# ATK_BC28_02.net
KiCad netlist of a schematic drawn in Altium Designer
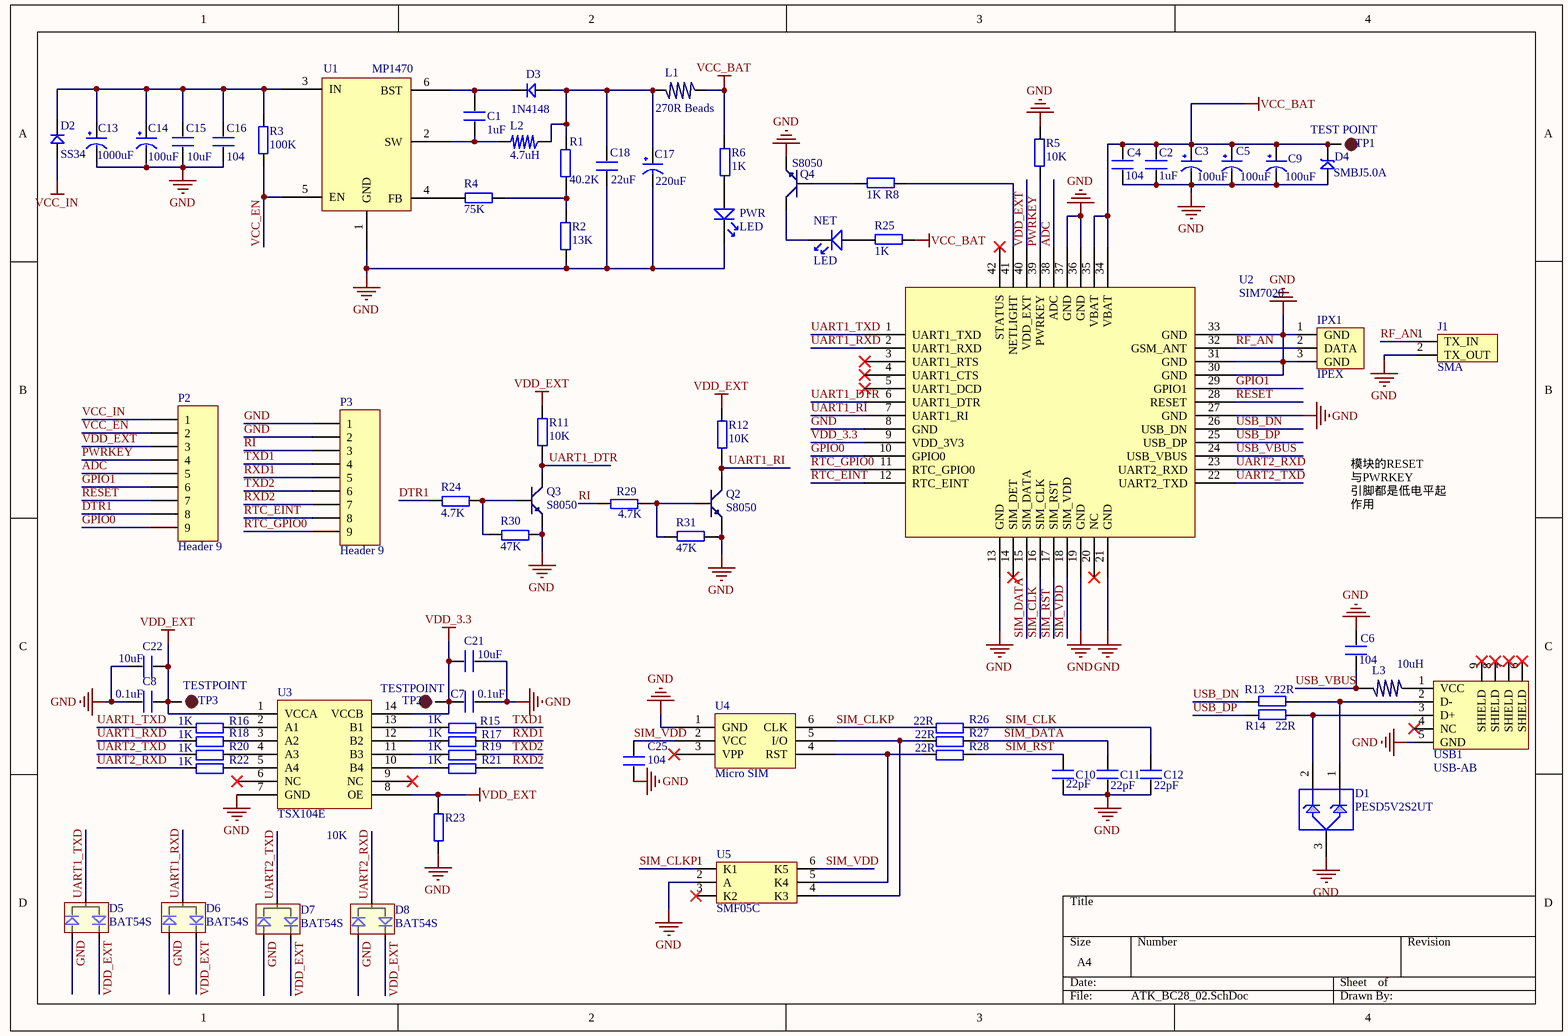
[diagram p0: ATK_BC28_02.SchDoc]

(export (version "E")
  (design (tool "Eeschema 10.0.6"))
  (components
    (comp (ref "C1") (value "1uF") (footprint "0603P") (libsource (lib "SIM7020") (part "C")))
    (comp (ref "C2") (value "1uF") (footprint "0603P") (libsource (lib "SIM7020") (part "C")))
    (comp (ref "C3") (value "100uF") (footprint "C3528") (libsource (lib "SIM7020") (part "CAP")))
    (comp (ref "C4") (value "104") (footprint "0603P") (libsource (lib "ALIENTEK_COMPONENT") (part "C")))
    (comp (ref "C5") (value "100uF") (footprint "C3528") (libsource (lib "SIM7020") (part "CAP")))
    (comp (ref "C6") (value "104") (footprint "0603P") (libsource (lib "ALIENTEK_COMPONENT") (part "C")))
    (comp (ref "C7") (value "0.1uF") (footprint "0603P") (libsource (lib "SIM7020") (part "C")))
    (comp (ref "C8") (value "0.1uF") (footprint "0603P") (libsource (lib "SIM7020") (part "C")))
    (comp (ref "C9") (value "100uF") (footprint "C3528") (libsource (lib "SIM7020") (part "CAP")))
    (comp (ref "C10") (value "22pF") (footprint "0402") (libsource (lib "ALIENTEK_COMPONENT") (part "C")))
    (comp (ref "C11") (value "22pF") (footprint "0402") (libsource (lib "ALIENTEK_COMPONENT") (part "C")))
    (comp (ref "C12") (value "22pF") (footprint "0402") (libsource (lib "ALIENTEK_COMPONENT") (part "C")))
    (comp (ref "C13")
      (value "1000uF")
      (footprint "CAP2.54")
      (libsource (lib "ALIENTEK_COMPONENT") (part "CAP"))
    )
    (comp (ref "C14") (value "100uF") (footprint "C3528") (libsource (lib "ALIENTEK_COMPONENT") (part "CAP")))
    (comp (ref "C15") (value "10uF") (footprint "0805") (libsource (lib "SIM7020") (part "C")))
    (comp (ref "C16") (value "104") (footprint "0603P") (libsource (lib "SIM7020") (part "C")))
    (comp (ref "C17") (value "220uF") (footprint "CC6.56.5") (libsource (lib "SIM7020") (part "CAP")))
    (comp (ref "C18") (value "22uF") (footprint "1206") (libsource (lib "SIM7020") (part "C")))
    (comp (ref "C21") (value "10uF") (footprint "0603P") (libsource (lib "SIM7020") (part "C")))
    (comp (ref "C22") (value "10uF") (footprint "0603P") (libsource (lib "SIM7020") (part "C")))
    (comp (ref "C25") (value "104") (footprint "0603P") (libsource (lib "ALIENTEK_COMPONENT") (part "C")))
    (comp (ref "D1")
      (value "PESD5V2S2UT")
      (footprint "SOT-23")
      (description "PESD5V2S2UT,SOT-23,NXP")
      (fields (field (name "Comment") "ESD-3"))
      (libsource (lib "02.MCU_KL25") (part "ESD-3"))
    )
    (comp (ref "D2")
      (value "SS34")
      (footprint "DIODE_3*5.3")
      (description "1N4148")
      (libsource (lib "alientek_sch_lib") (part "D"))
    )
    (comp (ref "D3") (value "1N4148") (footprint "DIODE_SOP") (libsource (lib "alientek_sch_lib") (part "D")))
    (comp (ref "D4")
      (value "SMBJ5.0A")
      (footprint "SMBJ")
      (description "TVS")
      (libsource (lib "ALIENTEK_COMPONENT") (part "SMBJ"))
    )
    (comp (ref "D5")
      (value "BAT54S")
      (footprint "SOT-23")
      (description "双肖特基二极管")
      (libsource (lib "ALIENTEK_COMPONENT") (part "BAT54S"))
    )
    (comp (ref "D6")
      (value "BAT54S")
      (footprint "SOT-23")
      (description "双肖特基二极管")
      (libsource (lib "ALIENTEK_COMPONENT") (part "BAT54S"))
    )
    (comp (ref "D7")
      (value "BAT54S")
      (footprint "SOT-23")
      (description "双肖特基二极管")
      (libsource (lib "ALIENTEK_COMPONENT") (part "BAT54S"))
    )
    (comp (ref "D8")
      (value "BAT54S")
      (footprint "SOT-23")
      (description "双肖特基二极管")
      (libsource (lib "ALIENTEK_COMPONENT") (part "BAT54S"))
    )
    (comp (ref "IPX1")
      (value "IPEX")
      (footprint "IPEX")
      (description "IPEX座")
      (libsource (lib "ATK_S1216F8_BD_V1.1") (part "IPEX"))
    )
    (comp (ref "J1")
      (value "SMA")
      (footprint "SMA-2")
      (description "SMA-2")
      (libsource (lib "SIM7020") (part "SMA-2"))
    )
    (comp (ref "L1") (value "270R Beads") (footprint "1206") (libsource (lib "SIM7020") (part "L")))
    (comp (ref "L2")
      (value "4.7uH")
      (footprint "L_CD43")
      (libsource (lib "ATK-7'TFTLCD电容触摸屏模块_V2.2") (part "L_SOP"))
    )
    (comp (ref "L3") (value "10uH") (footprint "0805") (libsource (lib "ALIENTEK_COMPONENT") (part "L")))
    (comp (ref "NET") (value "LED") (footprint "SMDLED") (libsource (lib "SIM7020") (part "LED")))
    (comp (ref "P2")
      (value "Header 9")
      (footprint "HDR1X9")
      (description "Header, 9-Pin")
      (fields (field (name "PUBLISHER") "Altium Limited"))
      (libsource (lib "Miscellaneous Connectors") (part "Header 9"))
    )
    (comp (ref "P3")
      (value "Header 9")
      (footprint "HDR1X9")
      (description "Header, 9-Pin")
      (fields (field (name "PUBLISHER") "Altium Limited"))
      (libsource (lib "Miscellaneous Connectors") (part "Header 9"))
    )
    (comp (ref "PWR") (value "LED") (footprint "SMDLED") (libsource (lib "SIM7020") (part "LED")))
    (comp (ref "Q2")
      (value "S8050")
      (footprint "SOT-23R")
      (description "8050/BCW846/BCW847")
      (libsource (lib "SIM7020") (part "NPN"))
    )
    (comp (ref "Q3")
      (value "S8050")
      (footprint "SOT-23R")
      (description "8050/BCW846/BCW847")
      (libsource (lib "SIM7020") (part "NPN"))
    )
    (comp (ref "Q4")
      (value "S8050")
      (footprint "SOT-23R")
      (description "8050/BCW846/BCW847")
      (libsource (lib "SIM7020") (part "NPN"))
    )
    (comp (ref "R1") (value "40.2K") (footprint "0603P") (libsource (lib "ALIENTEK_COMPONENT") (part "R")))
    (comp (ref "R2") (value "13K") (footprint "0603P") (libsource (lib "ALIENTEK_COMPONENT") (part "R")))
    (comp (ref "R3") (value "100K") (footprint "0603P") (libsource (lib "ALIENTEK_COMPONENT") (part "R")))
    (comp (ref "R4") (value "75K") (footprint "0603P") (libsource (lib "ALIENTEK_COMPONENT") (part "R")))
    (comp (ref "R5") (value "10K") (footprint "0603P") (libsource (lib "ALIENTEK_COMPONENT") (part "R")))
    (comp (ref "R6") (value "1K") (footprint "0603P") (libsource (lib "ALIENTEK_COMPONENT") (part "R")))
    (comp (ref "R8") (value "1K") (footprint "0603P") (libsource (lib "ALIENTEK_COMPONENT") (part "R")))
    (comp (ref "R11") (value "10K") (footprint "0603P") (libsource (lib "ALIENTEK_COMPONENT") (part "R")))
    (comp (ref "R12") (value "10K") (footprint "0603P") (libsource (lib "ALIENTEK_COMPONENT") (part "R")))
    (comp (ref "R13") (value "22R") (footprint "0603P") (libsource (lib "SIM7020") (part "R")))
    (comp (ref "R14") (value "22R") (footprint "0603P") (libsource (lib "SIM7020") (part "R")))
    (comp (ref "R15") (value "1K") (footprint "0603P") (libsource (lib "SIM7020") (part "R")))
    (comp (ref "R16") (value "1K") (footprint "0603P") (libsource (lib "SIM7020") (part "R")))
    (comp (ref "R17") (value "1K") (footprint "0603P") (libsource (lib "SIM7020") (part "R")))
    (comp (ref "R18") (value "1K") (footprint "0603P") (libsource (lib "SIM7020") (part "R")))
    (comp (ref "R19") (value "1K") (footprint "0603P") (libsource (lib "SIM7020") (part "R")))
    (comp (ref "R20") (value "1K") (footprint "0603P") (libsource (lib "SIM7020") (part "R")))
    (comp (ref "R21") (value "1K") (footprint "0603P") (libsource (lib "SIM7020") (part "R")))
    (comp (ref "R22") (value "1K") (footprint "0603P") (libsource (lib "SIM7020") (part "R")))
    (comp (ref "R23") (value "10K") (footprint "0603P") (libsource (lib "SIM7020") (part "R")))
    (comp (ref "R24") (value "4.7K") (footprint "0603P") (libsource (lib "ALIENTEK_COMPONENT") (part "R")))
    (comp (ref "R25") (value "1K") (footprint "0603P") (libsource (lib "ALIENTEK_COMPONENT") (part "R")))
    (comp (ref "R26") (value "22R") (footprint "0603P") (libsource (lib "SIM7020") (part "R")))
    (comp (ref "R27") (value "22R") (footprint "0603P") (libsource (lib "SIM7020") (part "R")))
    (comp (ref "R28") (value "22R") (footprint "0603P") (libsource (lib "SIM7020") (part "R")))
    (comp (ref "R29") (value "4.7K") (footprint "0603P") (libsource (lib "ALIENTEK_COMPONENT") (part "R")))
    (comp (ref "R30") (value "47K") (footprint "0603P") (libsource (lib "ALIENTEK_COMPONENT") (part "R")))
    (comp (ref "R31") (value "47K") (footprint "0603P") (libsource (lib "ALIENTEK_COMPONENT") (part "R")))
    (comp (ref "TP1")
      (value "TEST POINT")
      (footprint "TP-1.5")
      (description "测试点")
      (libsource (lib "ALIENTEK_COMPONENT") (part "TEST-POINT"))
    )
    (comp (ref "TP2")
      (value "TESTPOINT")
      (footprint "TP-1.5")
      (description "测试点")
      (libsource (lib "ALIENTEK_COMPONENT") (part "TEST-POINT"))
    )
    (comp (ref "TP3")
      (value "TESTPOINT")
      (footprint "TP-1.5")
      (description "测试点")
      (libsource (lib "ALIENTEK_COMPONENT") (part "TEST-POINT"))
    )
    (comp (ref "U1")
      (value "MP1470")
      (footprint "SOP23-6 - duplicate1")
      (libsource (lib "SIM7020") (part "MP1470"))
    )
    (comp (ref "U2")
      (value "SIM7020")
      (footprint "SIM7020")
      (description "NBloT")
      (libsource (lib "SIM7020") (part "SIM7020"))
    )
    (comp (ref "U3") (value "TSX104E") (footprint "TSX104E") (libsource (lib "SIM7020") (part "TSX104E")))
    (comp (ref "U4") (value "Micro SIM") (footprint "Micro SIM") (libsource (lib "plib") (part "Micro SIM")))
    (comp (ref "U5")
      (value "SMF05C")
      (footprint "SMF05C")
      (description "TVS")
      (libsource (lib "plib") (part "SMF05C"))
    )
    (comp (ref "USB1")
      (value "USB-AB")
      (footprint "USB_AB")
      (description "MicroUSB")
      (libsource (lib "ALIENTEK_COMPONENT") (part "USB-AB"))
    )
  )
  (nets
    (net (code "1") (name "/ADC") (class "Default")
      (node (ref "P2") (pin "5") (pinfunction "5_5") (pintype "passive"))
      (node (ref "U2") (pin "38") (pinfunction "ADC_38") (pintype "passive"))
    )
    (net (code "2") (name "/DTR1") (class "Default")
      (node (ref "P2") (pin "8") (pinfunction "8_8") (pintype "passive"))
      (node (ref "R24") (pin "1") (pintype "passive"))
    )
    (net (code "3") (name "/GPIO0") (class "Default")
      (node (ref "P2") (pin "9") (pinfunction "9_9") (pintype "passive"))
      (node (ref "U2") (pin "10") (pinfunction "GPIO0_10") (pintype "passive"))
    )
    (net (code "4") (name "/GPIO1") (class "Default")
      (node (ref "P2") (pin "6") (pinfunction "6_6") (pintype "passive"))
      (node (ref "U2") (pin "29") (pinfunction "GPIO1_29") (pintype "passive"))
    )
    (net (code "5") (name "/PWRKEY") (class "Default")
      (node (ref "P2") (pin "4") (pinfunction "4_4") (pintype "passive"))
      (node (ref "R5") (pin "2") (pintype "passive"))
      (node (ref "U2") (pin "39") (pinfunction "PWRKEY_39") (pintype "passive"))
    )
    (net (code "6") (name "/RESET") (class "Default")
      (node (ref "P2") (pin "7") (pinfunction "7_7") (pintype "passive"))
      (node (ref "U2") (pin "28") (pinfunction "RESET_28") (pintype "passive"))
    )
    (net (code "7") (name "/RF_AN") (class "Default")
      (node (ref "IPX1") (pin "2") (pinfunction "DATA_2") (pintype "passive"))
      (node (ref "J1") (pin "1") (pinfunction "TX_IN_1") (pintype "passive"))
      (node (ref "U2") (pin "32") (pinfunction "GSM_ANT_32") (pintype "passive"))
    )
    (net (code "8") (name "/RI") (class "Default")
      (node (ref "P3") (pin "3") (pinfunction "3_3") (pintype "passive"))
      (node (ref "R29") (pin "1") (pintype "passive"))
    )
    (net (code "9") (name "/RTC_EINT") (class "Default")
      (node (ref "P3") (pin "8") (pinfunction "8_8") (pintype "passive"))
      (node (ref "U2") (pin "12") (pinfunction "RTC_EINT_12") (pintype "passive"))
    )
    (net (code "10") (name "/RTC_GPIO0") (class "Default")
      (node (ref "P3") (pin "9") (pinfunction "9_9") (pintype "passive"))
      (node (ref "U2") (pin "11") (pinfunction "RTC_GPIO0_11") (pintype "passive"))
    )
    (net (code "11") (name "/RXD1") (class "Default")
      (node (ref "P3") (pin "5") (pinfunction "5_5") (pintype "passive"))
      (node (ref "R17") (pin "2") (pintype "passive"))
    )
    (net (code "12") (name "/RXD2") (class "Default")
      (node (ref "P3") (pin "7") (pinfunction "7_7") (pintype "passive"))
      (node (ref "R21") (pin "2") (pintype "passive"))
    )
    (net (code "13") (name "/SIM_CLK") (class "Default")
      (node (ref "C12") (pin "2") (pintype "passive"))
      (node (ref "R26") (pin "2") (pintype "passive"))
      (node (ref "U2") (pin "16") (pinfunction "SIM_CLK_16") (pintype "passive"))
    )
    (net (code "14") (name "/SIM_CLKP") (class "Default")
      (node (ref "R26") (pin "1") (pintype "passive"))
      (node (ref "U4") (pin "6") (pinfunction "CLK_6") (pintype "passive"))
      (node (ref "U5") (pin "1") (pinfunction "K1_1") (pintype "passive"))
    )
    (net (code "15") (name "/SIM_DATA") (class "Default")
      (node (ref "C11") (pin "2") (pintype "passive"))
      (node (ref "R27") (pin "2") (pintype "passive"))
      (node (ref "U2") (pin "15") (pinfunction "SIM_DATA_15") (pintype "passive"))
    )
    (net (code "16") (name "/SIM_RST") (class "Default")
      (node (ref "C10") (pin "1") (pintype "passive"))
      (node (ref "R28") (pin "2") (pintype "passive"))
      (node (ref "U2") (pin "17") (pinfunction "SIM_RST_17") (pintype "passive"))
    )
    (net (code "17") (name "/SIM_VDD") (class "Default")
      (node (ref "C25") (pin "2") (pintype "passive"))
      (node (ref "U2") (pin "18") (pinfunction "SIM_VDD_18") (pintype "passive"))
      (node (ref "U4") (pin "2") (pinfunction "VCC_2") (pintype "passive"))
      (node (ref "U5") (pin "6") (pinfunction "K5_6") (pintype "passive"))
    )
    (net (code "18") (name "/TXD1") (class "Default")
      (node (ref "P3") (pin "4") (pinfunction "4_4") (pintype "passive"))
      (node (ref "R15") (pin "2") (pintype "passive"))
    )
    (net (code "19") (name "/TXD2") (class "Default")
      (node (ref "P3") (pin "6") (pinfunction "6_6") (pintype "passive"))
      (node (ref "R19") (pin "2") (pintype "passive"))
    )
    (net (code "20") (name "/UART1_DTR") (class "Default")
      (node (ref "Q3") (pin "3") (pinfunction "C_3") (pintype "passive"))
      (node (ref "R11") (pin "1") (pintype "passive"))
      (node (ref "U2") (pin "6") (pinfunction "UART1_DTR_6") (pintype "passive"))
    )
    (net (code "21") (name "/UART1_RI") (class "Default")
      (node (ref "Q2") (pin "3") (pinfunction "C_3") (pintype "passive"))
      (node (ref "R12") (pin "1") (pintype "passive"))
      (node (ref "U2") (pin "7") (pinfunction "UART1_RI_7") (pintype "passive"))
    )
    (net (code "22") (name "/UART1_RXD") (class "Default")
      (node (ref "D6") (pin "3") (pintype "passive"))
      (node (ref "R18") (pin "1") (pintype "passive"))
      (node (ref "U2") (pin "2") (pinfunction "UART1_RXD_2") (pintype "passive"))
    )
    (net (code "23") (name "/UART1_TXD") (class "Default")
      (node (ref "D5") (pin "3") (pintype "passive"))
      (node (ref "R16") (pin "1") (pintype "passive"))
      (node (ref "U2") (pin "1") (pinfunction "UART1_TXD_1") (pintype "passive"))
    )
    (net (code "24") (name "/UART2_RXD") (class "Default")
      (node (ref "D8") (pin "3") (pintype "passive"))
      (node (ref "R22") (pin "1") (pintype "passive"))
      (node (ref "U2") (pin "23") (pinfunction "UART2_RXD_23") (pintype "passive"))
    )
    (net (code "25") (name "/UART2_TXD") (class "Default")
      (node (ref "D7") (pin "3") (pintype "passive"))
      (node (ref "R20") (pin "1") (pintype "passive"))
      (node (ref "U2") (pin "22") (pinfunction "UART2_TXD_22") (pintype "passive"))
    )
    (net (code "26") (name "/USB_DN") (class "Default")
      (node (ref "R13") (pin "2") (pintype "passive"))
      (node (ref "U2") (pin "26") (pinfunction "USB_DN_26") (pintype "passive"))
    )
    (net (code "27") (name "/USB_DP") (class "Default")
      (node (ref "R14") (pin "2") (pintype "passive"))
      (node (ref "U2") (pin "25") (pinfunction "USB_DP_25") (pintype "passive"))
    )
    (net (code "28") (name "/USB_VBUS") (class "Default")
      (node (ref "C6") (pin "1") (pintype "passive"))
      (node (ref "L3") (pin "2") (pintype "passive"))
      (node (ref "U2") (pin "24") (pinfunction "USB_VBUS_24") (pintype "passive"))
    )
    (net (code "29") (name "/VCC_EN") (class "Default")
      (node (ref "P2") (pin "2") (pinfunction "2_2") (pintype "passive"))
      (node (ref "R3") (pin "2") (pintype "passive"))
      (node (ref "U1") (pin "5") (pinfunction "EN_5") (pintype "passive"))
    )
    (net (code "30") (name "GND") (class "Default")
      (node (ref "C10") (pin "2") (pintype "passive"))
      (node (ref "C11") (pin "1") (pintype "passive"))
      (node (ref "C12") (pin "1") (pintype "passive"))
      (node (ref "C13") (pin "2") (pinfunction "GND_2") (pintype "passive"))
      (node (ref "C14") (pin "2") (pinfunction "GND_2") (pintype "passive"))
      (node (ref "C15") (pin "2") (pintype "passive"))
      (node (ref "C16") (pin "1") (pintype "passive"))
      (node (ref "C17") (pin "2") (pinfunction "GND_2") (pintype "passive"))
      (node (ref "C18") (pin "1") (pintype "passive"))
      (node (ref "C2") (pin "1") (pintype "passive"))
      (node (ref "C21") (pin "2") (pintype "passive"))
      (node (ref "C22") (pin "1") (pintype "passive"))
      (node (ref "C25") (pin "1") (pintype "passive"))
      (node (ref "C3") (pin "2") (pinfunction "GND_2") (pintype "passive"))
      (node (ref "C4") (pin "1") (pintype "passive"))
      (node (ref "C5") (pin "2") (pinfunction "GND_2") (pintype "passive"))
      (node (ref "C6") (pin "2") (pintype "passive"))
      (node (ref "C7") (pin "2") (pintype "passive"))
      (node (ref "C8") (pin "2") (pintype "passive"))
      (node (ref "C9") (pin "2") (pinfunction "GND_2") (pintype "passive"))
      (node (ref "D1") (pin "3") (pinfunction "3_3") (pintype "passive"))
      (node (ref "D4") (pin "1") (pintype "passive"))
      (node (ref "D5") (pin "1") (pintype "passive"))
      (node (ref "D6") (pin "1") (pintype "passive"))
      (node (ref "D7") (pin "1") (pintype "passive"))
      (node (ref "D8") (pin "1") (pintype "passive"))
      (node (ref "IPX1") (pin "1") (pinfunction "GND_1") (pintype "passive"))
      (node (ref "IPX1") (pin "3") (pinfunction "GND_3") (pintype "passive"))
      (node (ref "J1") (pin "2") (pinfunction "TX_OUT_2") (pintype "passive"))
      (node (ref "P3") (pin "1") (pinfunction "1_1") (pintype "passive"))
      (node (ref "P3") (pin "2") (pinfunction "2_2") (pintype "passive"))
      (node (ref "PWR") (pin "2") (pinfunction "2_2") (pintype "passive"))
      (node (ref "Q2") (pin "1") (pinfunction "E_1") (pintype "passive"))
      (node (ref "Q3") (pin "1") (pinfunction "E_1") (pintype "passive"))
      (node (ref "Q4") (pin "1") (pinfunction "E_1") (pintype "passive"))
      (node (ref "R2") (pin "2") (pintype "passive"))
      (node (ref "R23") (pin "1") (pintype "passive"))
      (node (ref "R30") (pin "2") (pintype "passive"))
      (node (ref "R31") (pin "1") (pintype "passive"))
      (node (ref "R5") (pin "1") (pintype "passive"))
      (node (ref "U1") (pin "1") (pinfunction "GND_1") (pintype "passive"))
      (node (ref "U2") (pin "13") (pinfunction "GND_13") (pintype "passive"))
      (node (ref "U2") (pin "19") (pinfunction "GND_19") (pintype "passive"))
      (node (ref "U2") (pin "21") (pinfunction "GND_21") (pintype "passive"))
      (node (ref "U2") (pin "27") (pinfunction "GND_27") (pintype "passive"))
      (node (ref "U2") (pin "30") (pinfunction "GND_30") (pintype "passive"))
      (node (ref "U2") (pin "31") (pinfunction "GND_31") (pintype "passive"))
      (node (ref "U2") (pin "33") (pinfunction "GND_33") (pintype "passive"))
      (node (ref "U2") (pin "36") (pinfunction "GND_36") (pintype "passive"))
      (node (ref "U2") (pin "37") (pinfunction "GND_37") (pintype "passive"))
      (node (ref "U2") (pin "8") (pinfunction "GND_8") (pintype "passive"))
      (node (ref "U3") (pin "7") (pinfunction "GND_7") (pintype "passive"))
      (node (ref "U4") (pin "1") (pinfunction "GND_1") (pintype "passive"))
      (node (ref "U5") (pin "2") (pinfunction "A_2") (pintype "passive"))
      (node (ref "USB1") (pin "5") (pinfunction "GND_5") (pintype "passive"))
    )
    (net (code "31") (name "Net-(C13-VCC)") (class "Default")
      (node (ref "C13") (pin "1") (pinfunction "VCC_1") (pintype "passive"))
      (node (ref "C14") (pin "1") (pinfunction "VCC_1") (pintype "passive"))
      (node (ref "C15") (pin "1") (pintype "passive"))
      (node (ref "C16") (pin "2") (pintype "passive"))
      (node (ref "D2") (pin "2") (pintype "passive"))
      (node (ref "R3") (pin "1") (pintype "passive"))
      (node (ref "U1") (pin "3") (pinfunction "IN_3") (pintype "passive"))
    )
    (net (code "32") (name "Net-(C17-VCC)") (class "Default")
      (node (ref "C17") (pin "1") (pinfunction "VCC_1") (pintype "passive"))
      (node (ref "C18") (pin "2") (pintype "passive"))
      (node (ref "D3") (pin "1") (pintype "passive"))
      (node (ref "L1") (pin "2") (pintype "passive"))
      (node (ref "L2") (pin "1") (pinfunction "1_1") (pintype "passive"))
      (node (ref "R1") (pin "1") (pintype "passive"))
    )
    (net (code "33") (name "Net-(NET-Pad1)") (class "Default")
      (node (ref "NET") (pin "1") (pinfunction "1_1") (pintype "passive"))
      (node (ref "R25") (pin "2") (pintype "passive"))
    )
    (net (code "34") (name "Net-(PWR-Pad1)") (class "Default")
      (node (ref "PWR") (pin "1") (pinfunction "1_1") (pintype "passive"))
      (node (ref "R6") (pin "1") (pintype "passive"))
    )
    (net (code "35") (name "Net-(Q2-B)") (class "Default")
      (node (ref "Q2") (pin "2") (pinfunction "B_2") (pintype "passive"))
      (node (ref "R29") (pin "2") (pintype "passive"))
      (node (ref "R31") (pin "2") (pintype "passive"))
    )
    (net (code "36") (name "Net-(Q3-B)") (class "Default")
      (node (ref "Q3") (pin "2") (pinfunction "B_2") (pintype "passive"))
      (node (ref "R24") (pin "2") (pintype "passive"))
      (node (ref "R30") (pin "1") (pintype "passive"))
    )
    (net (code "37") (name "Net-(Q4-B)") (class "Default")
      (node (ref "Q4") (pin "2") (pinfunction "B_2") (pintype "passive"))
      (node (ref "R8") (pin "2") (pintype "passive"))
    )
    (net (code "38") (name "Net-(Q4-C)") (class "Default")
      (node (ref "NET") (pin "2") (pinfunction "2_2") (pintype "passive"))
      (node (ref "Q4") (pin "3") (pinfunction "C_3") (pintype "passive"))
    )
    (net (code "39") (name "Net-(R1-Pad2)") (class "Default")
      (node (ref "R1") (pin "2") (pintype "passive"))
      (node (ref "R2") (pin "1") (pintype "passive"))
      (node (ref "R4") (pin "1") (pintype "passive"))
    )
    (net (code "40") (name "Net-(U1-BST)") (class "Default")
      (node (ref "C1") (pin "1") (pintype "passive"))
      (node (ref "D3") (pin "2") (pintype "passive"))
      (node (ref "U1") (pin "6") (pinfunction "BST_6") (pintype "passive"))
    )
    (net (code "41") (name "Net-(U1-FB)") (class "Default")
      (node (ref "R4") (pin "2") (pintype "passive"))
      (node (ref "U1") (pin "4") (pinfunction "FB_4") (pintype "passive"))
    )
    (net (code "42") (name "Net-(U1-SW)") (class "Default")
      (node (ref "C1") (pin "2") (pintype "passive"))
      (node (ref "L2") (pin "2") (pinfunction "2_2") (pintype "passive"))
      (node (ref "U1") (pin "2") (pinfunction "SW_2") (pintype "passive"))
    )
    (net (code "43") (name "Net-(U2-NETLIGHT)") (class "Default")
      (node (ref "R8") (pin "1") (pintype "passive"))
      (node (ref "U2") (pin "41") (pinfunction "NETLIGHT_41") (pintype "passive"))
    )
    (net (code "44") (name "Net-(U3-A1)") (class "Default")
      (node (ref "R16") (pin "2") (pintype "passive"))
      (node (ref "U3") (pin "2") (pinfunction "A1_2") (pintype "passive"))
    )
    (net (code "45") (name "Net-(U3-A2)") (class "Default")
      (node (ref "R18") (pin "2") (pintype "passive"))
      (node (ref "U3") (pin "3") (pinfunction "A2_3") (pintype "passive"))
    )
    (net (code "46") (name "Net-(U3-A3)") (class "Default")
      (node (ref "R20") (pin "2") (pintype "passive"))
      (node (ref "U3") (pin "4") (pinfunction "A3_4") (pintype "passive"))
    )
    (net (code "47") (name "Net-(U3-A4)") (class "Default")
      (node (ref "R22") (pin "2") (pintype "passive"))
      (node (ref "U3") (pin "5") (pinfunction "A4_5") (pintype "passive"))
    )
    (net (code "48") (name "Net-(U3-B1)") (class "Default")
      (node (ref "R15") (pin "1") (pintype "passive"))
      (node (ref "U3") (pin "13") (pinfunction "B1_13") (pintype "passive"))
    )
    (net (code "49") (name "Net-(U3-B2)") (class "Default")
      (node (ref "R17") (pin "1") (pintype "passive"))
      (node (ref "U3") (pin "12") (pinfunction "B2_12") (pintype "passive"))
    )
    (net (code "50") (name "Net-(U3-B3)") (class "Default")
      (node (ref "R19") (pin "1") (pintype "passive"))
      (node (ref "U3") (pin "11") (pinfunction "B3_11") (pintype "passive"))
    )
    (net (code "51") (name "Net-(U3-B4)") (class "Default")
      (node (ref "R21") (pin "1") (pintype "passive"))
      (node (ref "U3") (pin "10") (pinfunction "B4_10") (pintype "passive"))
    )
    (net (code "52") (name "Net-(U4-I{slash}O)") (class "Default")
      (node (ref "R27") (pin "1") (pintype "passive"))
      (node (ref "U4") (pin "5") (pinfunction "I/O_5") (pintype "passive"))
      (node (ref "U5") (pin "4") (pinfunction "K3_4") (pintype "passive"))
    )
    (net (code "53") (name "Net-(U4-RST)") (class "Default")
      (node (ref "R28") (pin "1") (pintype "passive"))
      (node (ref "U4") (pin "4") (pinfunction "RST_4") (pintype "passive"))
      (node (ref "U5") (pin "5") (pinfunction "K4_5") (pintype "passive"))
    )
    (net (code "54") (name "Net-(USB1-D+)") (class "Default")
      (node (ref "D1") (pin "2") (pinfunction "2_2") (pintype "passive"))
      (node (ref "R14") (pin "1") (pintype "passive"))
      (node (ref "USB1") (pin "3") (pinfunction "D+_3") (pintype "passive"))
    )
    (net (code "55") (name "Net-(USB1-D-)") (class "Default")
      (node (ref "D1") (pin "1") (pinfunction "1_1") (pintype "passive"))
      (node (ref "R13") (pin "1") (pintype "passive"))
      (node (ref "USB1") (pin "2") (pinfunction "D-_2") (pintype "passive"))
    )
    (net (code "56") (name "Net-(USB1-VCC)") (class "Default")
      (node (ref "L3") (pin "1") (pintype "passive"))
      (node (ref "USB1") (pin "1") (pinfunction "VCC_1") (pintype "passive"))
    )
    (net (code "57") (name "VCC_BAT") (class "Default")
      (node (ref "C2") (pin "2") (pintype "passive"))
      (node (ref "C3") (pin "1") (pinfunction "VCC_1") (pintype "passive"))
      (node (ref "C4") (pin "2") (pintype "passive"))
      (node (ref "C5") (pin "1") (pinfunction "VCC_1") (pintype "passive"))
      (node (ref "C9") (pin "1") (pinfunction "VCC_1") (pintype "passive"))
      (node (ref "D4") (pin "2") (pintype "passive"))
      (node (ref "L1") (pin "1") (pintype "passive"))
      (node (ref "R25") (pin "1") (pintype "passive"))
      (node (ref "R6") (pin "2") (pintype "passive"))
      (node (ref "TP1") (pin "1") (pinfunction "1_1") (pintype "passive"))
      (node (ref "U2") (pin "34") (pinfunction "VBAT_34") (pintype "passive"))
      (node (ref "U2") (pin "35") (pinfunction "VBAT_35") (pintype "passive"))
    )
    (net (code "58") (name "VCC_IN") (class "Default")
      (node (ref "D2") (pin "1") (pintype "passive"))
      (node (ref "P2") (pin "1") (pinfunction "1_1") (pintype "passive"))
    )
    (net (code "59") (name "VDD_3.3") (class "Default")
      (node (ref "C21") (pin "1") (pintype "passive"))
      (node (ref "C7") (pin "1") (pintype "passive"))
      (node (ref "TP2") (pin "1") (pinfunction "1_1") (pintype "passive"))
      (node (ref "U2") (pin "9") (pinfunction "VDD_3V3_9") (pintype "passive"))
      (node (ref "U3") (pin "14") (pinfunction "VCCB_14") (pintype "passive"))
    )
    (net (code "60") (name "VDD_EXT") (class "Default")
      (node (ref "C22") (pin "2") (pintype "passive"))
      (node (ref "C8") (pin "1") (pintype "passive"))
      (node (ref "D5") (pin "2") (pintype "passive"))
      (node (ref "D6") (pin "2") (pintype "passive"))
      (node (ref "D7") (pin "2") (pintype "passive"))
      (node (ref "D8") (pin "2") (pintype "passive"))
      (node (ref "P2") (pin "3") (pinfunction "3_3") (pintype "passive"))
      (node (ref "R11") (pin "2") (pintype "passive"))
      (node (ref "R12") (pin "2") (pintype "passive"))
      (node (ref "R23") (pin "2") (pintype "passive"))
      (node (ref "TP3") (pin "1") (pinfunction "1_1") (pintype "passive"))
      (node (ref "U2") (pin "40") (pinfunction "VDD_EXT_40") (pintype "passive"))
      (node (ref "U3") (pin "1") (pinfunction "VCCA_1") (pintype "passive"))
      (node (ref "U3") (pin "8") (pinfunction "OE_8") (pintype "passive"))
    )
    (net (code "61") (name "unconnected-(U2-NC-Pad20)") (class "Default")
      (node (ref "U2") (pin "20") (pinfunction "NC_20") (pintype "passive+no_connect"))
    )
    (net (code "62") (name "unconnected-(U2-SIM_DET-Pad14)") (class "Default")
      (node (ref "U2") (pin "14") (pinfunction "SIM_DET_14") (pintype "passive+no_connect"))
    )
    (net (code "63") (name "unconnected-(U2-STATUS-Pad42)") (class "Default")
      (node (ref "U2") (pin "42") (pinfunction "STATUS_42") (pintype "passive+no_connect"))
    )
    (net (code "64") (name "unconnected-(U2-UART1_CTS-Pad4)") (class "Default")
      (node (ref "U2") (pin "4") (pinfunction "UART1_CTS_4") (pintype "passive+no_connect"))
    )
    (net (code "65") (name "unconnected-(U2-UART1_DCD-Pad5)") (class "Default")
      (node (ref "U2") (pin "5") (pinfunction "UART1_DCD_5") (pintype "passive+no_connect"))
    )
    (net (code "66") (name "unconnected-(U2-UART1_RTS-Pad3)") (class "Default")
      (node (ref "U2") (pin "3") (pinfunction "UART1_RTS_3") (pintype "passive+no_connect"))
    )
    (net (code "67") (name "unconnected-(U3-NC-Pad6)") (class "Default")
      (node (ref "U3") (pin "6") (pinfunction "NC_6") (pintype "passive+no_connect"))
    )
    (net (code "68") (name "unconnected-(U3-NC-Pad9)") (class "Default")
      (node (ref "U3") (pin "9") (pinfunction "NC_9") (pintype "passive+no_connect"))
    )
    (net (code "69") (name "unconnected-(U4-VPP-Pad3)") (class "Default")
      (node (ref "U4") (pin "3") (pinfunction "VPP_3") (pintype "passive+no_connect"))
    )
    (net (code "70") (name "unconnected-(U5-K2-Pad3)") (class "Default")
      (node (ref "U5") (pin "3") (pinfunction "K2_3") (pintype "passive+no_connect"))
    )
    (net (code "71") (name "unconnected-(USB1-NC-Pad4)") (class "Default")
      (node (ref "USB1") (pin "4") (pinfunction "NC_4") (pintype "passive+no_connect"))
    )
    (net (code "72") (name "unconnected-(USB1-SHIELD-Pad6)") (class "Default")
      (node (ref "USB1") (pin "6") (pinfunction "SHIELD_6") (pintype "passive+no_connect"))
    )
    (net (code "73") (name "unconnected-(USB1-SHIELD-Pad7)") (class "Default")
      (node (ref "USB1") (pin "7") (pinfunction "SHIELD_7") (pintype "passive+no_connect"))
    )
    (net (code "74") (name "unconnected-(USB1-SHIELD-Pad8)") (class "Default")
      (node (ref "USB1") (pin "8") (pinfunction "SHIELD_8") (pintype "passive+no_connect"))
    )
    (net (code "75") (name "unconnected-(USB1-SHIELD-Pad9)") (class "Default")
      (node (ref "USB1") (pin "9") (pinfunction "SHIELD_9") (pintype "passive+no_connect"))
    )
  )
)
